# MXR2_v1.net
KiCad netlist of a schematic drawn in EAGLE
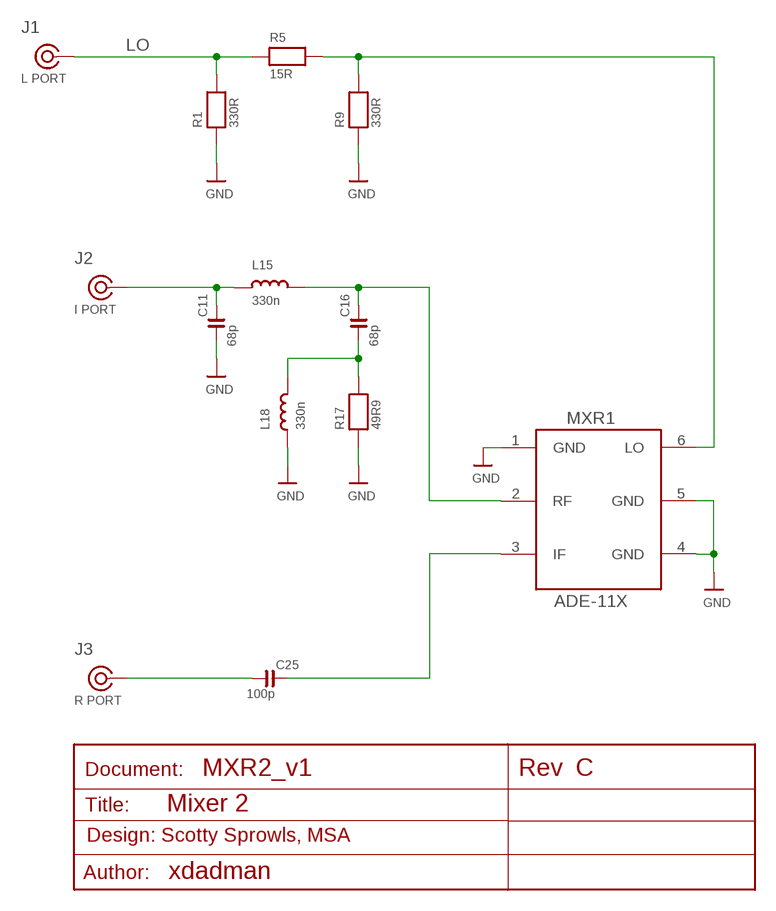
[diagram p0: schematic, sheet 1]

(export (version "E")
  (design (tool "Eeschema 10.0.6"))
  (components
    (comp (ref "C11")
      (value "68p")
      (footprint "eagle-import:C0805")
      (libsource (lib "eagle-import") (part "C080568P"))
    )
    (comp (ref "C16")
      (value "68p")
      (footprint "eagle-import:C0805")
      (libsource (lib "eagle-import") (part "C080568P"))
    )
    (comp (ref "C25")
      (value "100p")
      (footprint "eagle-import:C0805")
      (libsource (lib "eagle-import") (part "C0805100P"))
    )
    (comp (ref "J1")
      (value "L PORT")
      (footprint "eagle-import:SLIM_COAX_PAD")
      (libsource (lib "eagle-import") (part "COAX"))
    )
    (comp (ref "J2")
      (value "I PORT")
      (footprint "eagle-import:SLIM_COAX_PAD")
      (libsource (lib "eagle-import") (part "COAX"))
    )
    (comp (ref "J3")
      (value "R PORT")
      (footprint "eagle-import:SLIM_COAX_PAD")
      (libsource (lib "eagle-import") (part "COAX"))
    )
    (comp (ref "L15")
      (value "330n")
      (footprint "eagle-import:L805")
      (libsource (lib "eagle-import") (part "L0805330N"))
    )
    (comp (ref "L18")
      (value "330n")
      (footprint "eagle-import:L805")
      (libsource (lib "eagle-import") (part "L0805330N"))
    )
    (comp (ref "MXR1")
      (value "ADE-11X")
      (footprint "eagle-import:ADE-11X")
      (libsource (lib "eagle-import") (part "ADE-11X"))
    )
    (comp (ref "R1")
      (value "330R")
      (footprint "eagle-import:R0805")
      (libsource (lib "eagle-import") (part "R0805330R"))
    )
    (comp (ref "R5")
      (value "15R")
      (footprint "eagle-import:0805")
      (libsource (lib "eagle-import") (part "R080515R"))
    )
    (comp (ref "R9")
      (value "330R")
      (footprint "eagle-import:R0805")
      (libsource (lib "eagle-import") (part "R0805330R"))
    )
    (comp (ref "R17")
      (value "49R9")
      (footprint "eagle-import:R0805")
      (libsource (lib "eagle-import") (part "R080549R9"))
    )
  )
  (nets
    (net (code "1") (name "/LO") (class "Default")
      (node (ref "J1") (pin "SIG") (pinfunction "1_SIG") (pintype "passive"))
      (node (ref "R1") (pin "2") (pinfunction "2_2") (pintype "passive"))
      (node (ref "R5") (pin "1") (pinfunction "1_1") (pintype "passive"))
    )
    (net (code "2") (name "GND") (class "Default")
      (node (ref "C11") (pin "1") (pinfunction "1_1") (pintype "passive"))
      (node (ref "L18") (pin "1") (pinfunction "1_1") (pintype "passive"))
      (node (ref "MXR1") (pin "1") (pinfunction "GND_1") (pintype "bidirectional"))
      (node (ref "MXR1") (pin "4") (pinfunction "GND_4") (pintype "bidirectional"))
      (node (ref "MXR1") (pin "5") (pinfunction "GND_5") (pintype "bidirectional"))
      (node (ref "R1") (pin "1") (pinfunction "1_1") (pintype "passive"))
      (node (ref "R17") (pin "1") (pinfunction "1_1") (pintype "passive"))
      (node (ref "R9") (pin "1") (pinfunction "1_1") (pintype "passive"))
    )
    (net (code "3") (name "Net-(C16-Pad1)") (class "Default")
      (node (ref "C16") (pin "1") (pinfunction "1_1") (pintype "passive"))
      (node (ref "L18") (pin "2") (pinfunction "2_2") (pintype "passive"))
      (node (ref "R17") (pin "2") (pinfunction "2_2") (pintype "passive"))
    )
    (net (code "4") (name "Net-(J2A-1)") (class "Default")
      (node (ref "C11") (pin "2") (pinfunction "2_2") (pintype "passive"))
      (node (ref "J2") (pin "SIG") (pinfunction "1_SIG") (pintype "passive"))
      (node (ref "L15") (pin "1") (pinfunction "1_1") (pintype "passive"))
    )
    (net (code "5") (name "Net-(J3A-1)") (class "Default")
      (node (ref "C25") (pin "1") (pinfunction "1_1") (pintype "passive"))
      (node (ref "J3") (pin "SIG") (pinfunction "1_SIG") (pintype "passive"))
    )
    (net (code "6") (name "Net-(MXR1-IF)") (class "Default")
      (node (ref "C25") (pin "2") (pinfunction "2_2") (pintype "passive"))
      (node (ref "MXR1") (pin "3") (pinfunction "IF_3") (pintype "bidirectional"))
    )
    (net (code "7") (name "Net-(MXR1-LO)") (class "Default")
      (node (ref "MXR1") (pin "6") (pinfunction "LO_6") (pintype "bidirectional"))
      (node (ref "R5") (pin "2") (pinfunction "2_2") (pintype "passive"))
      (node (ref "R9") (pin "2") (pinfunction "2_2") (pintype "passive"))
    )
    (net (code "8") (name "Net-(MXR1-RF)") (class "Default")
      (node (ref "C16") (pin "2") (pinfunction "2_2") (pintype "passive"))
      (node (ref "L15") (pin "2") (pinfunction "2_2") (pintype "passive"))
      (node (ref "MXR1") (pin "2") (pinfunction "RF_2") (pintype "bidirectional"))
    )
  )
)
